# NoTricks.net
KiCad netlist of a schematic drawn in EAGLE
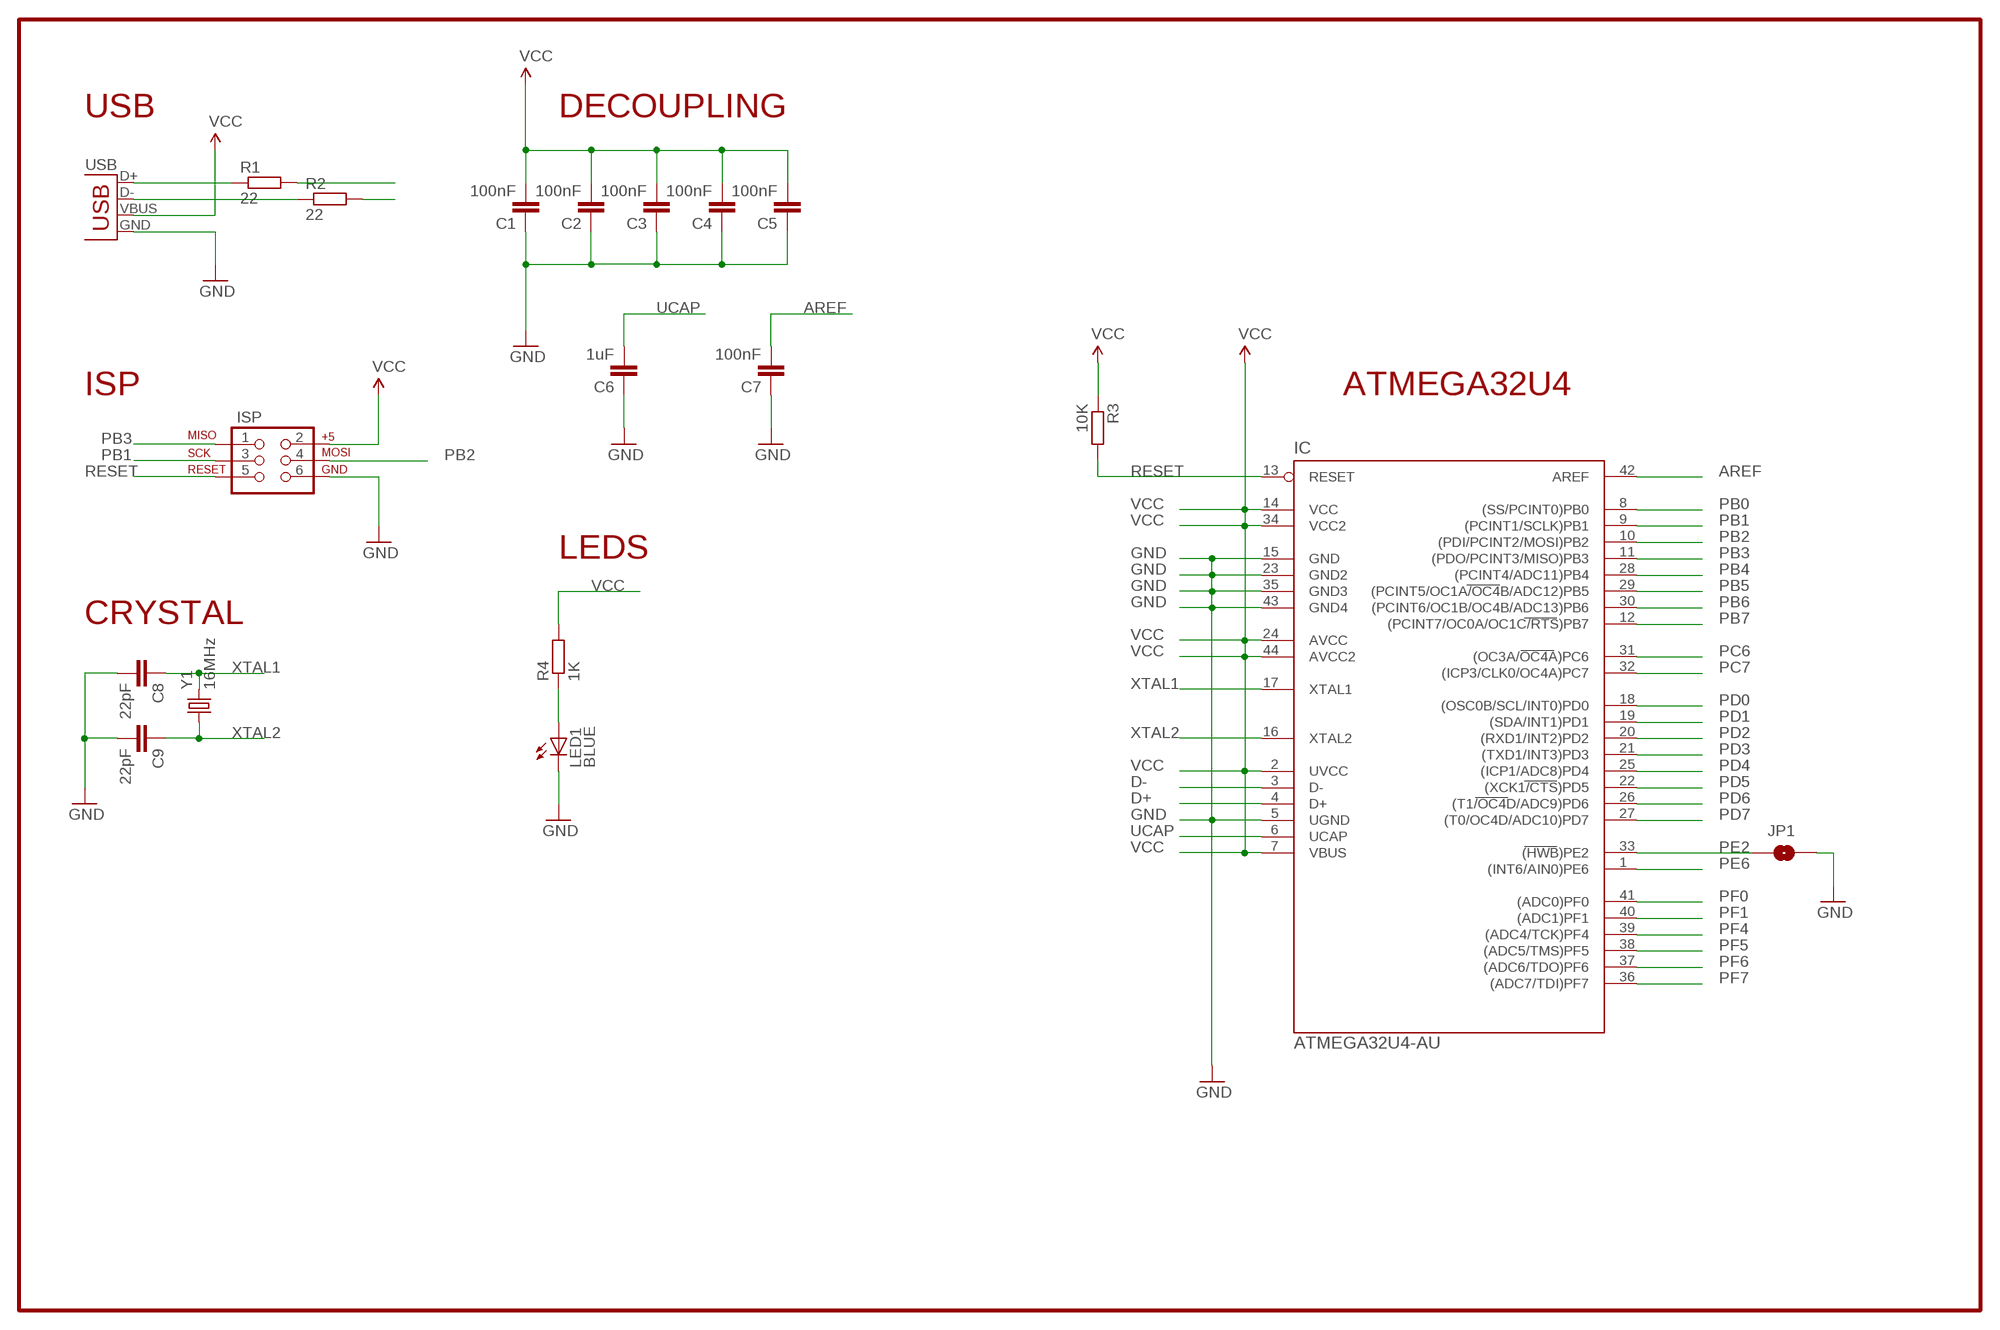
[diagram p0: schematic, sheet 1]

(export (version "E")
  (design (tool "Eeschema 10.0.6"))
  (components
    (comp (ref "C1")
      (value "100nF")
      (footprint "eagle-import:C0805")
      (libsource (lib "eagle-import") (part "C-EUC0805"))
    )
    (comp (ref "C2")
      (value "100nF")
      (footprint "eagle-import:C0805")
      (libsource (lib "eagle-import") (part "C-EUC0805"))
    )
    (comp (ref "C3")
      (value "100nF")
      (footprint "eagle-import:C0805")
      (libsource (lib "eagle-import") (part "C-EUC0805"))
    )
    (comp (ref "C4")
      (value "100nF")
      (footprint "eagle-import:C0805")
      (libsource (lib "eagle-import") (part "C-EUC0805"))
    )
    (comp (ref "C5")
      (value "100nF")
      (footprint "eagle-import:C0805")
      (libsource (lib "eagle-import") (part "C-EUC0805"))
    )
    (comp (ref "C6")
      (value "1uF")
      (footprint "eagle-import:C0805")
      (libsource (lib "eagle-import") (part "C-EUC0805"))
    )
    (comp (ref "C7")
      (value "100nF")
      (footprint "eagle-import:C0805")
      (libsource (lib "eagle-import") (part "C-EUC0805"))
    )
    (comp (ref "C8")
      (value "22pF")
      (footprint "eagle-import:C0805")
      (libsource (lib "eagle-import") (part "C-EUC0805"))
    )
    (comp (ref "C9")
      (value "22pF")
      (footprint "eagle-import:C0805")
      (libsource (lib "eagle-import") (part "C-EUC0805"))
    )
    (comp (ref "IC")
      (value "ATMEGA32U4-AU")
      (footprint "eagle-import:TQFP44")
      (libsource (lib "eagle-import") (part "ATMEGA32U4-AU"))
    )
    (comp (ref "ISP")
      (value "AVR_SPI_PRG_6PTH")
      (footprint "eagle-import:2X3")
      (libsource (lib "eagle-import") (part "AVR_SPI_PRG_6PTH"))
    )
    (comp (ref "JP1")
      (value "JUMPER-PAD-2-NO")
      (footprint "eagle-import:PAD-JUMPER-2-NO_NO_SILK")
      (libsource (lib "eagle-import") (part "JUMPER-PAD-2-NO"))
    )
    (comp (ref "LED1")
      (value "BLUE")
      (footprint "eagle-import:LED-1206")
      (libsource (lib "eagle-import") (part "LED1206"))
    )
    (comp (ref "R1")
      (value "22")
      (footprint "eagle-import:R0603")
      (libsource (lib "eagle-import") (part "R-EU_R0603"))
    )
    (comp (ref "R2")
      (value "22")
      (footprint "eagle-import:R0603")
      (libsource (lib "eagle-import") (part "R-EU_R0603"))
    )
    (comp (ref "R3")
      (value "10K")
      (footprint "eagle-import:R0603")
      (libsource (lib "eagle-import") (part "R-EU_R0603"))
    )
    (comp (ref "R4")
      (value "1K")
      (footprint "eagle-import:R0603")
      (libsource (lib "eagle-import") (part "R-EU_R0603"))
    )
    (comp (ref "USB")
      (value "USB-A-H")
      (footprint "eagle-import:USB-A-H")
      (libsource (lib "eagle-import") (part "USB-A-H"))
    )
    (comp (ref "Y1")
      (value "16MHz")
      (footprint "eagle-import:CRYSTAL-SMD-5X3")
      (libsource (lib "eagle-import") (part "CRYSTALCRYSTAL-SMD-5X3-12MHZ"))
    )
  )
  (nets
    (net (code "1") (name "/AREF") (class "Default")
      (node (ref "C7") (pin "2") (pinfunction "2_2") (pintype "passive"))
      (node (ref "IC") (pin "42") (pinfunction "AREF_42") (pintype "bidirectional"))
    )
    (net (code "2") (name "/D+") (class "Default")
      (node (ref "IC") (pin "4") (pinfunction "D+_4") (pintype "bidirectional"))
      (node (ref "R1") (pin "2") (pinfunction "2_2") (pintype "passive"))
    )
    (net (code "3") (name "/D-") (class "Default")
      (node (ref "IC") (pin "3") (pinfunction "D-_3") (pintype "bidirectional"))
      (node (ref "R2") (pin "2") (pinfunction "2_2") (pintype "passive"))
    )
    (net (code "4") (name "/PB0") (class "Default")
      (node (ref "IC") (pin "8") (pinfunction "(SS/PCINT0)PB0_8") (pintype "bidirectional"))
    )
    (net (code "5") (name "/PB1") (class "Default")
      (node (ref "IC") (pin "9") (pinfunction "(PCINT1/SCLK)PB1_9") (pintype "bidirectional"))
      (node (ref "ISP") (pin "3") (pinfunction "3_3") (pintype "passive"))
    )
    (net (code "6") (name "/PB2") (class "Default")
      (node (ref "IC") (pin "10") (pinfunction "(PDI/PCINT2/MOSI)PB2_10") (pintype "bidirectional"))
      (node (ref "ISP") (pin "4") (pinfunction "4_4") (pintype "passive"))
    )
    (net (code "7") (name "/PB3") (class "Default")
      (node (ref "IC") (pin "11") (pinfunction "(PDO/PCINT3/MISO)PB3_11") (pintype "bidirectional"))
      (node (ref "ISP") (pin "1") (pinfunction "1_1") (pintype "passive"))
    )
    (net (code "8") (name "/PB4") (class "Default")
      (node (ref "IC") (pin "28") (pinfunction "(PCINT4/ADC11)PB4_28") (pintype "bidirectional"))
    )
    (net (code "9") (name "/PB5") (class "Default")
      (node (ref "IC") (pin "29") (pinfunction "(PCINT5/OC1A/OC4B/ADC12)PB5_29") (pintype "bidirectional"))
    )
    (net (code "10") (name "/PB6") (class "Default")
      (node (ref "IC") (pin "30") (pinfunction "(PCINT6/OC1B/OC4B/ADC13)PB6_30") (pintype "bidirectional"))
    )
    (net (code "11") (name "/PB7") (class "Default")
      (node (ref "IC") (pin "12") (pinfunction "(PCINT7/OC0A/OC1C/RTS)PB7_12") (pintype "bidirectional"))
    )
    (net (code "12") (name "/PC6") (class "Default")
      (node (ref "IC") (pin "31") (pinfunction "(OC3A/OC4A)PC6_31") (pintype "bidirectional"))
    )
    (net (code "13") (name "/PC7") (class "Default")
      (node (ref "IC") (pin "32") (pinfunction "(ICP3/CLK0/OC4A)PC7_32") (pintype "bidirectional"))
    )
    (net (code "14") (name "/PD0") (class "Default")
      (node (ref "IC") (pin "18") (pinfunction "(OSC0B/SCL/INT0)PD0_18") (pintype "bidirectional"))
    )
    (net (code "15") (name "/PD1") (class "Default")
      (node (ref "IC") (pin "19") (pinfunction "(SDA/INT1)PD1_19") (pintype "bidirectional"))
    )
    (net (code "16") (name "/PD2") (class "Default")
      (node (ref "IC") (pin "20") (pinfunction "(RXD1/INT2)PD2_20") (pintype "bidirectional"))
    )
    (net (code "17") (name "/PD3") (class "Default")
      (node (ref "IC") (pin "21") (pinfunction "(TXD1/INT3)PD3_21") (pintype "bidirectional"))
    )
    (net (code "18") (name "/PD4") (class "Default")
      (node (ref "IC") (pin "25") (pinfunction "(ICP1/ADC8)PD4_25") (pintype "bidirectional"))
    )
    (net (code "19") (name "/PD5") (class "Default")
      (node (ref "IC") (pin "22") (pinfunction "(XCK1/CTS)PD5_22") (pintype "bidirectional"))
    )
    (net (code "20") (name "/PD6") (class "Default")
      (node (ref "IC") (pin "26") (pinfunction "(T1/OC4D/ADC9)PD6_26") (pintype "bidirectional"))
    )
    (net (code "21") (name "/PD7") (class "Default")
      (node (ref "IC") (pin "27") (pinfunction "(T0/OC4D/ADC10)PD7_27") (pintype "bidirectional"))
    )
    (net (code "22") (name "/PE2") (class "Default")
      (node (ref "IC") (pin "33") (pinfunction "(HWB)PE2_33") (pintype "bidirectional"))
      (node (ref "JP1") (pin "1") (pinfunction "1_1") (pintype "passive"))
    )
    (net (code "23") (name "/PE6") (class "Default")
      (node (ref "IC") (pin "1") (pinfunction "(INT6/AIN0)PE6_1") (pintype "bidirectional"))
    )
    (net (code "24") (name "/PF0") (class "Default")
      (node (ref "IC") (pin "41") (pinfunction "(ADC0)PF0_41") (pintype "bidirectional"))
    )
    (net (code "25") (name "/PF1") (class "Default")
      (node (ref "IC") (pin "40") (pinfunction "(ADC1)PF1_40") (pintype "bidirectional"))
    )
    (net (code "26") (name "/PF4") (class "Default")
      (node (ref "IC") (pin "39") (pinfunction "(ADC4/TCK)PF4_39") (pintype "bidirectional"))
    )
    (net (code "27") (name "/PF5") (class "Default")
      (node (ref "IC") (pin "38") (pinfunction "(ADC5/TMS)PF5_38") (pintype "bidirectional"))
    )
    (net (code "28") (name "/PF6") (class "Default")
      (node (ref "IC") (pin "37") (pinfunction "(ADC6/TDO)PF6_37") (pintype "bidirectional"))
    )
    (net (code "29") (name "/PF7") (class "Default")
      (node (ref "IC") (pin "36") (pinfunction "(ADC7/TDI)PF7_36") (pintype "bidirectional"))
    )
    (net (code "30") (name "/RESET") (class "Default")
      (node (ref "IC") (pin "13") (pinfunction "RESET_13") (pintype "bidirectional"))
      (node (ref "ISP") (pin "5") (pinfunction "5_5") (pintype "passive"))
      (node (ref "R3") (pin "2") (pinfunction "2_2") (pintype "passive"))
    )
    (net (code "31") (name "/UCAP") (class "Default")
      (node (ref "C6") (pin "2") (pinfunction "2_2") (pintype "passive"))
      (node (ref "IC") (pin "6") (pinfunction "UCAP_6") (pintype "bidirectional"))
    )
    (net (code "32") (name "/XTAL1") (class "Default")
      (node (ref "C8") (pin "1") (pinfunction "1_1") (pintype "passive"))
      (node (ref "IC") (pin "17") (pinfunction "XTAL1_17") (pintype "bidirectional"))
      (node (ref "Y1") (pin "3") (pinfunction "2_3") (pintype "passive"))
    )
    (net (code "33") (name "/XTAL2") (class "Default")
      (node (ref "C9") (pin "1") (pinfunction "1_1") (pintype "passive"))
      (node (ref "IC") (pin "16") (pinfunction "XTAL2_16") (pintype "bidirectional"))
      (node (ref "Y1") (pin "1") (pinfunction "1_1") (pintype "passive"))
    )
    (net (code "34") (name "GND") (class "Default")
      (node (ref "C1") (pin "1") (pinfunction "1_1") (pintype "passive"))
      (node (ref "C2") (pin "1") (pinfunction "1_1") (pintype "passive"))
      (node (ref "C3") (pin "1") (pinfunction "1_1") (pintype "passive"))
      (node (ref "C4") (pin "1") (pinfunction "1_1") (pintype "passive"))
      (node (ref "C5") (pin "1") (pinfunction "1_1") (pintype "passive"))
      (node (ref "C6") (pin "1") (pinfunction "1_1") (pintype "passive"))
      (node (ref "C7") (pin "1") (pinfunction "1_1") (pintype "passive"))
      (node (ref "C8") (pin "2") (pinfunction "2_2") (pintype "passive"))
      (node (ref "C9") (pin "2") (pinfunction "2_2") (pintype "passive"))
      (node (ref "IC") (pin "15") (pinfunction "GND_15") (pintype "bidirectional"))
      (node (ref "IC") (pin "23") (pinfunction "GND2_23") (pintype "bidirectional"))
      (node (ref "IC") (pin "35") (pinfunction "GND3_35") (pintype "bidirectional"))
      (node (ref "IC") (pin "43") (pinfunction "GND4_43") (pintype "bidirectional"))
      (node (ref "IC") (pin "5") (pinfunction "UGND_5") (pintype "bidirectional"))
      (node (ref "ISP") (pin "6") (pinfunction "6_6") (pintype "passive"))
      (node (ref "JP1") (pin "2") (pinfunction "2_2") (pintype "passive"))
      (node (ref "LED1") (pin "C") (pinfunction "C_C") (pintype "passive"))
      (node (ref "USB") (pin "GND") (pinfunction "GND_GND") (pintype "bidirectional"))
    )
    (net (code "35") (name "Net-(LED1-PadA)") (class "Default")
      (node (ref "LED1") (pin "A") (pinfunction "A_A") (pintype "passive"))
      (node (ref "R4") (pin "1") (pinfunction "1_1") (pintype "passive"))
    )
    (net (code "36") (name "Net-(R1-Pad1)") (class "Default")
      (node (ref "R1") (pin "1") (pinfunction "1_1") (pintype "passive"))
      (node (ref "USB") (pin "D+") (pinfunction "D+_D+") (pintype "bidirectional"))
    )
    (net (code "37") (name "Net-(R2-Pad1)") (class "Default")
      (node (ref "R2") (pin "1") (pinfunction "1_1") (pintype "passive"))
      (node (ref "USB") (pin "D-") (pinfunction "D-_D-") (pintype "bidirectional"))
    )
    (net (code "38") (name "VCC") (class "Default")
      (node (ref "C1") (pin "2") (pinfunction "2_2") (pintype "passive"))
      (node (ref "C2") (pin "2") (pinfunction "2_2") (pintype "passive"))
      (node (ref "C3") (pin "2") (pinfunction "2_2") (pintype "passive"))
      (node (ref "C4") (pin "2") (pinfunction "2_2") (pintype "passive"))
      (node (ref "C5") (pin "2") (pinfunction "2_2") (pintype "passive"))
      (node (ref "IC") (pin "14") (pinfunction "VCC_14") (pintype "bidirectional"))
      (node (ref "IC") (pin "2") (pinfunction "UVCC_2") (pintype "bidirectional"))
      (node (ref "IC") (pin "24") (pinfunction "AVCC_24") (pintype "bidirectional"))
      (node (ref "IC") (pin "34") (pinfunction "VCC2_34") (pintype "bidirectional"))
      (node (ref "IC") (pin "44") (pinfunction "AVCC2_44") (pintype "bidirectional"))
      (node (ref "IC") (pin "7") (pinfunction "VBUS_7") (pintype "bidirectional"))
      (node (ref "ISP") (pin "2") (pinfunction "2_2") (pintype "passive"))
      (node (ref "R3") (pin "1") (pinfunction "1_1") (pintype "passive"))
      (node (ref "R4") (pin "2") (pinfunction "2_2") (pintype "passive"))
      (node (ref "USB") (pin "VBUS") (pinfunction "VBUS_VBUS") (pintype "bidirectional"))
    )
  )
)
